# LOXpixel.net
KiCad netlist of a schematic drawn in EAGLE
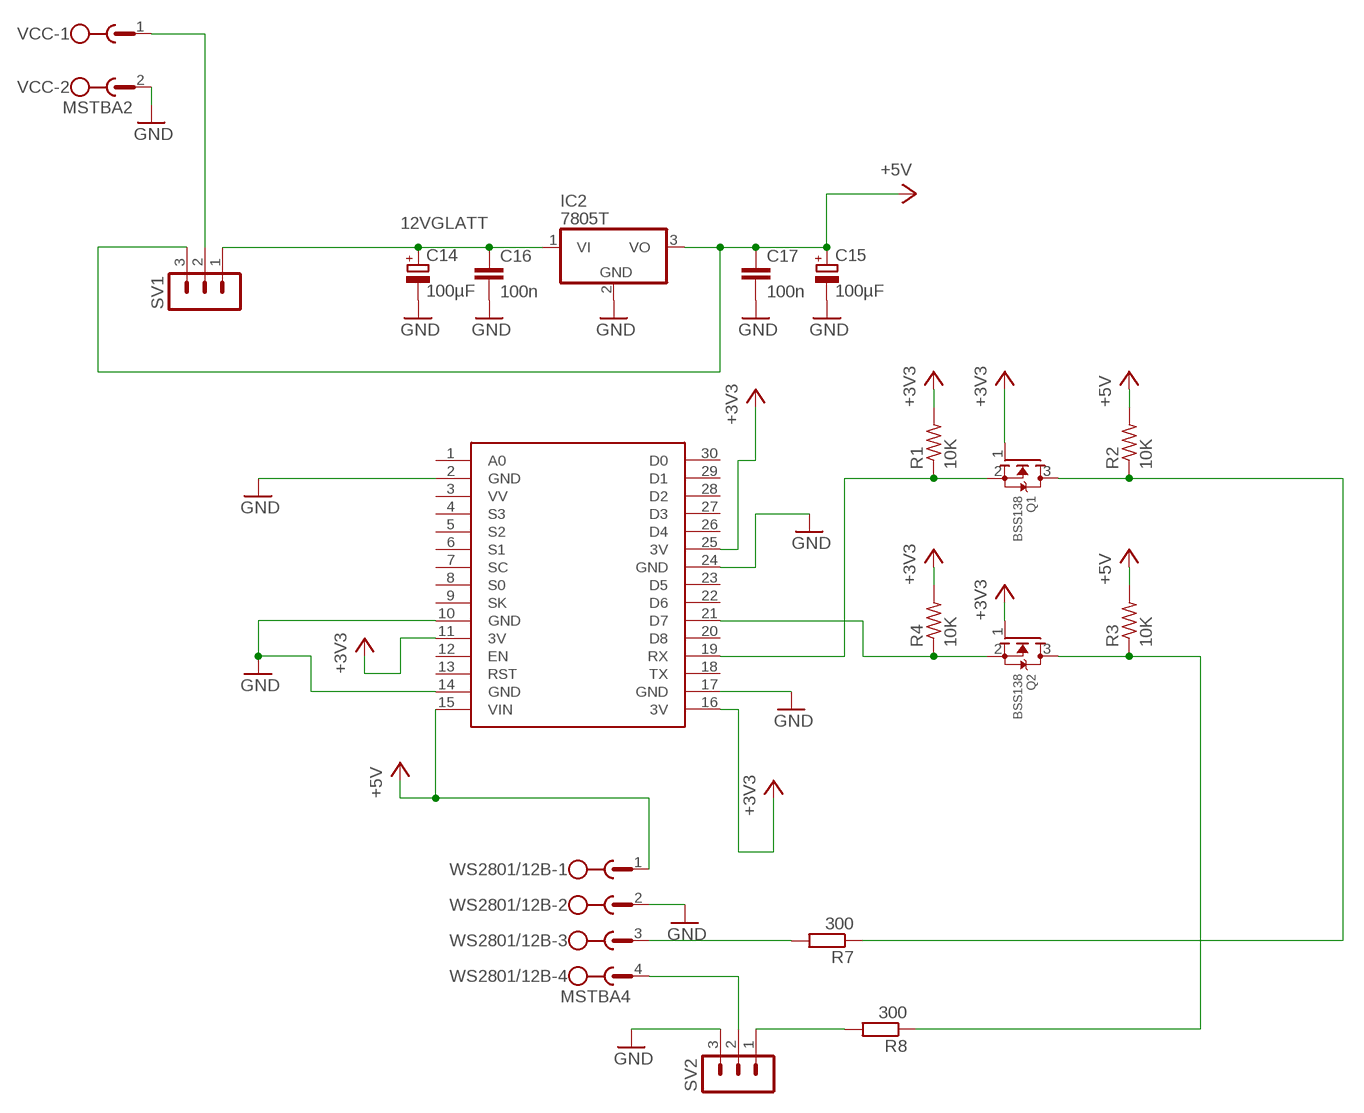
[diagram p0: schematic, sheet 1]

(export (version "E")
  (design (tool "Eeschema 10.0.6"))
  (components
    (comp (ref "C14")
      (value "100µF")
      (footprint "eagle-import:150CLZ-0810")
      (libsource (lib "eagle-import") (part "CPOL-EU150CLZ-0810"))
    )
    (comp (ref "C15")
      (value "100µF")
      (footprint "eagle-import:150CLZ-0810")
      (libsource (lib "eagle-import") (part "CPOL-EU150CLZ-0810"))
    )
    (comp (ref "C16")
      (value "100n")
      (footprint "eagle-import:C0805")
      (libsource (lib "eagle-import") (part "C-EUC0805"))
    )
    (comp (ref "C17")
      (value "100n")
      (footprint "eagle-import:C0805")
      (libsource (lib "eagle-import") (part "C-EUC0805"))
    )
    (comp (ref "IC2")
      (value "7805T")
      (footprint "eagle-import:TO220H")
      (libsource (lib "eagle-import") (part "78T05"))
    )
    (comp (ref "Q1")
      (value "BSS138")
      (footprint "eagle-import:SOT23")
      (libsource (lib "eagle-import") (part "MOSFET-NREFLOW"))
    )
    (comp (ref "Q2")
      (value "BSS138")
      (footprint "eagle-import:SOT23")
      (libsource (lib "eagle-import") (part "MOSFET-NREFLOW"))
    )
    (comp (ref "R1")
      (value "10K")
      (footprint "eagle-import:R0805")
      (libsource (lib "eagle-import") (part "R-US_R0805"))
    )
    (comp (ref "R2")
      (value "10K")
      (footprint "eagle-import:R0805")
      (libsource (lib "eagle-import") (part "R-US_R0805"))
    )
    (comp (ref "R3")
      (value "10K")
      (footprint "eagle-import:R0805")
      (libsource (lib "eagle-import") (part "R-US_R0805"))
    )
    (comp (ref "R4")
      (value "10K")
      (footprint "eagle-import:R0805")
      (libsource (lib "eagle-import") (part "R-US_R0805"))
    )
    (comp (ref "R7")
      (value "300")
      (footprint "eagle-import:R0805")
      (libsource (lib "eagle-import") (part "R-EU_R0805"))
    )
    (comp (ref "R8")
      (value "300")
      (footprint "eagle-import:R0805")
      (libsource (lib "eagle-import") (part "R-EU_R0805"))
    )
    (comp (ref "SV1")
      (value "MA03-1")
      (footprint "eagle-import:MA03-1")
      (libsource (lib "eagle-import") (part "MA03-1"))
    )
    (comp (ref "SV2")
      (value "MA03-1")
      (footprint "eagle-import:MA03-1")
      (libsource (lib "eagle-import") (part "MA03-1"))
    )
    (comp (ref "U$1")
      (value "NODEMCU")
      (footprint "eagle-import:NODEMCU")
      (libsource (lib "eagle-import") (part "NODEMCU"))
    )
    (comp (ref "VCC")
      (value "MSTBA2")
      (footprint "eagle-import:MSTBA2")
      (fields (field (name "MF") "FARNELL") (field (name "MPN") "1757242"))
      (libsource (lib "eagle-import") (part "MSTBA2"))
    )
    (comp (ref "WS2801/12B")
      (value "MSTBA4")
      (footprint "eagle-import:MSTBA4")
      (fields (field (name "MF") "FARNELL") (field (name "MPN") "1757268"))
      (libsource (lib "eagle-import") (part "MSTBA4"))
    )
  )
  (nets
    (net (code "1") (name "+3V3") (class "Default")
      (node (ref "Q1") (pin "1") (pinfunction "G_1") (pintype "bidirectional"))
      (node (ref "Q2") (pin "1") (pinfunction "G_1") (pintype "bidirectional"))
      (node (ref "R1") (pin "2") (pinfunction "2_2") (pintype "passive"))
      (node (ref "R4") (pin "2") (pinfunction "2_2") (pintype "passive"))
      (node (ref "U$1") (pin "11") (pinfunction "3V_11") (pintype "power_in"))
      (node (ref "U$1") (pin "16") (pinfunction "3V_16") (pintype "power_in"))
      (node (ref "U$1") (pin "25") (pinfunction "3V_25") (pintype "power_in"))
    )
    (net (code "2") (name "+5V") (class "Default")
      (node (ref "C15") (pin "+") (pinfunction "+_+") (pintype "passive"))
      (node (ref "C17") (pin "1") (pinfunction "1_1") (pintype "passive"))
      (node (ref "IC2") (pin "3") (pinfunction "VO_3") (pintype "passive"))
      (node (ref "R2") (pin "2") (pinfunction "2_2") (pintype "passive"))
      (node (ref "R3") (pin "2") (pinfunction "2_2") (pintype "passive"))
      (node (ref "SV1") (pin "3") (pinfunction "3_3") (pintype "passive"))
      (node (ref "U$1") (pin "15") (pinfunction "VIN_15") (pintype "bidirectional"))
      (node (ref "WS2801/12B") (pin "1") (pinfunction "1_1") (pintype "passive"))
    )
    (net (code "3") (name "/12VGLATT") (class "Default")
      (node (ref "C14") (pin "+") (pinfunction "+_+") (pintype "passive"))
      (node (ref "C16") (pin "1") (pinfunction "1_1") (pintype "passive"))
      (node (ref "IC2") (pin "1") (pinfunction "VI_1") (pintype "input"))
      (node (ref "SV1") (pin "1") (pinfunction "1_1") (pintype "passive"))
    )
    (net (code "4") (name "GND") (class "Default")
      (node (ref "C14") (pin "-") (pinfunction "-_-") (pintype "passive"))
      (node (ref "C15") (pin "-") (pinfunction "-_-") (pintype "passive"))
      (node (ref "C16") (pin "2") (pinfunction "2_2") (pintype "passive"))
      (node (ref "C17") (pin "2") (pinfunction "2_2") (pintype "passive"))
      (node (ref "IC2") (pin "2") (pinfunction "GND_2") (pintype "passive"))
      (node (ref "SV2") (pin "3") (pinfunction "3_3") (pintype "passive"))
      (node (ref "U$1") (pin "10") (pinfunction "GND_10") (pintype "power_in"))
      (node (ref "U$1") (pin "14") (pinfunction "GND_14") (pintype "power_in"))
      (node (ref "U$1") (pin "17") (pinfunction "GND_17") (pintype "power_in"))
      (node (ref "U$1") (pin "2") (pinfunction "GND_2") (pintype "power_in"))
      (node (ref "U$1") (pin "24") (pinfunction "GND_24") (pintype "power_in"))
      (node (ref "VCC") (pin "2") (pinfunction "1_2") (pintype "passive"))
      (node (ref "WS2801/12B") (pin "2") (pinfunction "1_2") (pintype "passive"))
    )
    (net (code "5") (name "Net-(Q1-D)") (class "Default")
      (node (ref "Q1") (pin "3") (pinfunction "D_3") (pintype "bidirectional"))
      (node (ref "R2") (pin "1") (pinfunction "1_1") (pintype "passive"))
      (node (ref "R7") (pin "1") (pinfunction "1_1") (pintype "passive"))
    )
    (net (code "6") (name "Net-(Q1-S)") (class "Default")
      (node (ref "Q1") (pin "2") (pinfunction "S_2") (pintype "bidirectional"))
      (node (ref "R1") (pin "1") (pinfunction "1_1") (pintype "passive"))
      (node (ref "U$1") (pin "19") (pinfunction "RX_19") (pintype "bidirectional"))
    )
    (net (code "7") (name "Net-(Q2-D)") (class "Default")
      (node (ref "Q2") (pin "3") (pinfunction "D_3") (pintype "bidirectional"))
      (node (ref "R3") (pin "1") (pinfunction "1_1") (pintype "passive"))
      (node (ref "R8") (pin "1") (pinfunction "1_1") (pintype "passive"))
    )
    (net (code "8") (name "Net-(Q2-S)") (class "Default")
      (node (ref "Q2") (pin "2") (pinfunction "S_2") (pintype "bidirectional"))
      (node (ref "R4") (pin "1") (pinfunction "1_1") (pintype "passive"))
      (node (ref "U$1") (pin "21") (pinfunction "D7_21") (pintype "bidirectional"))
    )
    (net (code "9") (name "Net-(R8-Pad2)") (class "Default")
      (node (ref "R8") (pin "2") (pinfunction "2_2") (pintype "passive"))
      (node (ref "SV2") (pin "1") (pinfunction "1_1") (pintype "passive"))
    )
    (net (code "10") (name "Net-(SV1-Pad2)") (class "Default")
      (node (ref "SV1") (pin "2") (pinfunction "2_2") (pintype "passive"))
      (node (ref "VCC") (pin "1") (pinfunction "1_1") (pintype "passive"))
    )
    (net (code "11") (name "Net-(WS2801/12BC-1)") (class "Default")
      (node (ref "R7") (pin "2") (pinfunction "2_2") (pintype "passive"))
      (node (ref "WS2801/12B") (pin "3") (pinfunction "1_3") (pintype "passive"))
    )
    (net (code "12") (name "Net-(WS2801/12BD-1)") (class "Default")
      (node (ref "SV2") (pin "2") (pinfunction "2_2") (pintype "passive"))
      (node (ref "WS2801/12B") (pin "4") (pinfunction "1_4") (pintype "passive"))
    )
    (net (code "13") (name "unconnected-(U$1-A0-Pad1)") (class "Default")
      (node (ref "U$1") (pin "1") (pinfunction "A0_1") (pintype "bidirectional"))
    )
    (net (code "14") (name "unconnected-(U$1-D0-Pad30)") (class "Default")
      (node (ref "U$1") (pin "30") (pinfunction "D0_30") (pintype "bidirectional"))
    )
    (net (code "15") (name "unconnected-(U$1-D1-Pad29)") (class "Default")
      (node (ref "U$1") (pin "29") (pinfunction "D1_29") (pintype "bidirectional"))
    )
    (net (code "16") (name "unconnected-(U$1-D2-Pad28)") (class "Default")
      (node (ref "U$1") (pin "28") (pinfunction "D2_28") (pintype "bidirectional"))
    )
    (net (code "17") (name "unconnected-(U$1-D3-Pad27)") (class "Default")
      (node (ref "U$1") (pin "27") (pinfunction "D3_27") (pintype "bidirectional"))
    )
    (net (code "18") (name "unconnected-(U$1-D4-Pad26)") (class "Default")
      (node (ref "U$1") (pin "26") (pinfunction "D4_26") (pintype "bidirectional"))
    )
    (net (code "19") (name "unconnected-(U$1-D5-Pad23)") (class "Default")
      (node (ref "U$1") (pin "23") (pinfunction "D5_23") (pintype "bidirectional"))
    )
    (net (code "20") (name "unconnected-(U$1-D6-Pad22)") (class "Default")
      (node (ref "U$1") (pin "22") (pinfunction "D6_22") (pintype "bidirectional"))
    )
    (net (code "21") (name "unconnected-(U$1-D8-Pad20)") (class "Default")
      (node (ref "U$1") (pin "20") (pinfunction "D8_20") (pintype "bidirectional"))
    )
    (net (code "22") (name "unconnected-(U$1-EN-Pad12)") (class "Default")
      (node (ref "U$1") (pin "12") (pinfunction "EN_12") (pintype "bidirectional"))
    )
    (net (code "23") (name "unconnected-(U$1-RST-Pad13)") (class "Default")
      (node (ref "U$1") (pin "13") (pinfunction "RST_13") (pintype "bidirectional"))
    )
    (net (code "24") (name "unconnected-(U$1-S0-Pad8)") (class "Default")
      (node (ref "U$1") (pin "8") (pinfunction "S0_8") (pintype "bidirectional"))
    )
    (net (code "25") (name "unconnected-(U$1-S1-Pad6)") (class "Default")
      (node (ref "U$1") (pin "6") (pinfunction "S1_6") (pintype "bidirectional"))
    )
    (net (code "26") (name "unconnected-(U$1-S2-Pad5)") (class "Default")
      (node (ref "U$1") (pin "5") (pinfunction "S2_5") (pintype "bidirectional"))
    )
    (net (code "27") (name "unconnected-(U$1-S3-Pad4)") (class "Default")
      (node (ref "U$1") (pin "4") (pinfunction "S3_4") (pintype "bidirectional"))
    )
    (net (code "28") (name "unconnected-(U$1-SC-Pad7)") (class "Default")
      (node (ref "U$1") (pin "7") (pinfunction "SC_7") (pintype "bidirectional"))
    )
    (net (code "29") (name "unconnected-(U$1-SK-Pad9)") (class "Default")
      (node (ref "U$1") (pin "9") (pinfunction "SK_9") (pintype "bidirectional"))
    )
    (net (code "30") (name "unconnected-(U$1-TX-Pad18)") (class "Default")
      (node (ref "U$1") (pin "18") (pinfunction "TX_18") (pintype "bidirectional"))
    )
    (net (code "31") (name "unconnected-(U$1-VV-Pad3)") (class "Default")
      (node (ref "U$1") (pin "3") (pinfunction "VV_3") (pintype "bidirectional"))
    )
  )
)
